# dexterity.net
KiCad netlist of a schematic drawn in EAGLE
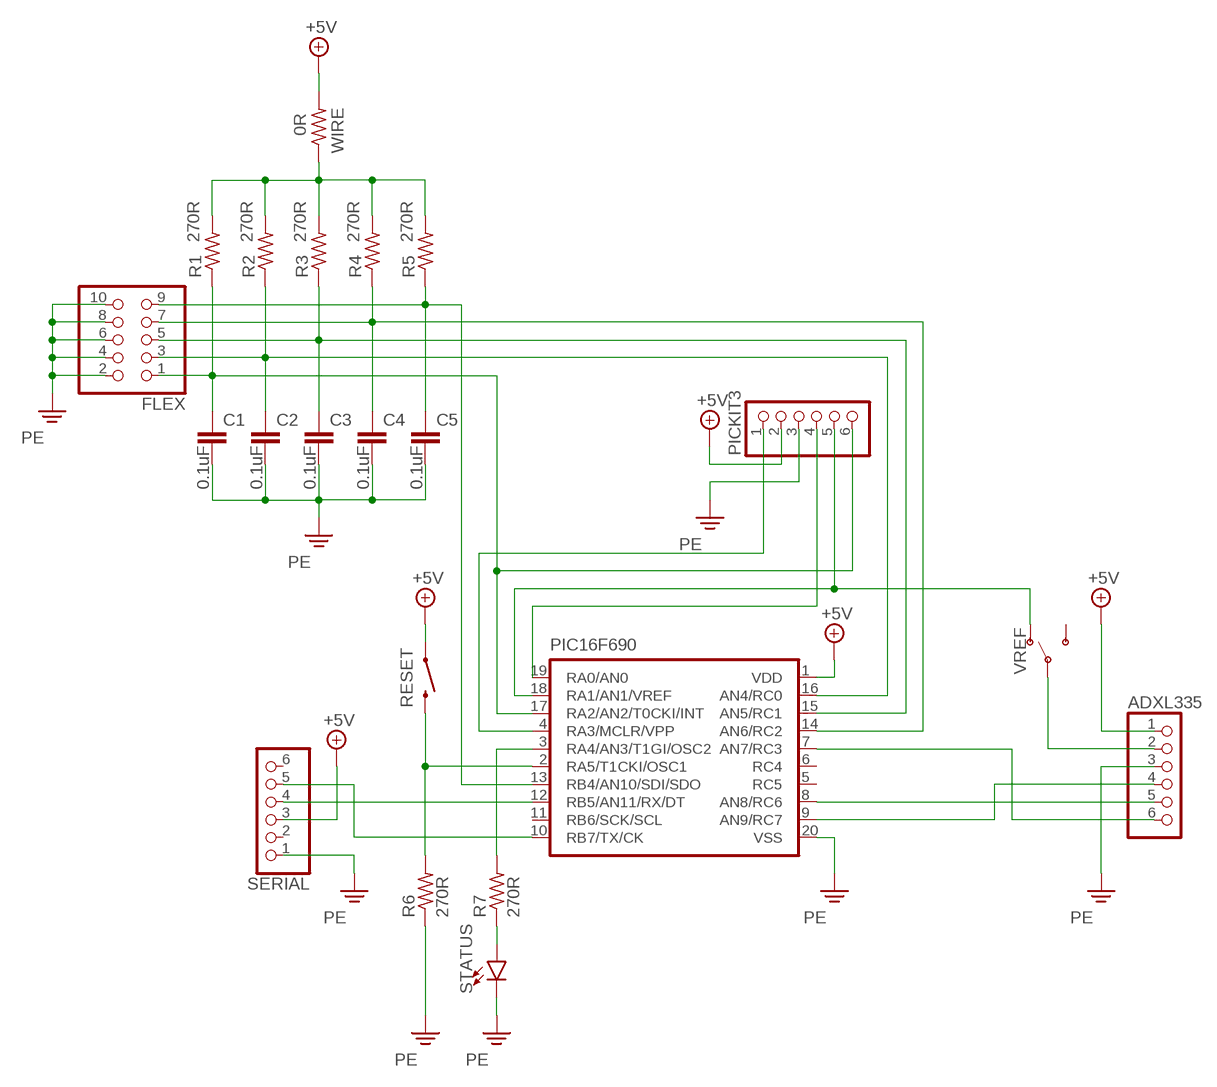
[diagram p0: schematic, sheet 1]

(export (version "E")
  (design (tool "Eeschema 10.0.6"))
  (components
    (comp (ref "ADXL335")
      (value "PINHD-1X6/90")
      (footprint "eagle-import:1X06_90")
      (libsource (lib "eagle-import") (part "PINHD-1X6/90"))
    )
    (comp (ref "C1")
      (value "0.1uF")
      (footprint "eagle-import:C050-025X075")
      (libsource (lib "eagle-import") (part "C-EU050-025X075"))
    )
    (comp (ref "C2")
      (value "0.1uF")
      (footprint "eagle-import:C050-025X075")
      (libsource (lib "eagle-import") (part "C-EU050-025X075"))
    )
    (comp (ref "C3")
      (value "0.1uF")
      (footprint "eagle-import:C050-025X075")
      (libsource (lib "eagle-import") (part "C-EU050-025X075"))
    )
    (comp (ref "C4")
      (value "0.1uF")
      (footprint "eagle-import:C050-025X075")
      (libsource (lib "eagle-import") (part "C-EU050-025X075"))
    )
    (comp (ref "C5")
      (value "0.1uF")
      (footprint "eagle-import:C050-025X075")
      (libsource (lib "eagle-import") (part "C-EU050-025X075"))
    )
    (comp (ref "FLEX")
      (value "PINHD-2X5/90")
      (footprint "eagle-import:2X05_90")
      (libsource (lib "eagle-import") (part "PINHD-2X5/90"))
    )
    (comp (ref "PIC16F690")
      (value "PIC16F6XX")
      (footprint "eagle-import:DIL20")
      (libsource (lib "eagle-import") (part "PIC16F6XX"))
    )
    (comp (ref "PICKIT3")
      (value "PINHD-1X6")
      (footprint "eagle-import:1X06")
      (libsource (lib "eagle-import") (part "PINHD-1X6"))
    )
    (comp (ref "R1")
      (value "270R")
      (footprint "eagle-import:0207_7")
      (libsource (lib "eagle-import") (part "R-US_0207/7"))
    )
    (comp (ref "R2")
      (value "270R")
      (footprint "eagle-import:0207_7")
      (libsource (lib "eagle-import") (part "R-US_0207/7"))
    )
    (comp (ref "R3")
      (value "270R")
      (footprint "eagle-import:0207_7")
      (libsource (lib "eagle-import") (part "R-US_0207/7"))
    )
    (comp (ref "R4")
      (value "270R")
      (footprint "eagle-import:0207_7")
      (libsource (lib "eagle-import") (part "R-US_0207/7"))
    )
    (comp (ref "R5")
      (value "270R")
      (footprint "eagle-import:0207_7")
      (libsource (lib "eagle-import") (part "R-US_0207/7"))
    )
    (comp (ref "R6")
      (value "270R")
      (footprint "eagle-import:0207_7")
      (libsource (lib "eagle-import") (part "R-US_0207/7"))
    )
    (comp (ref "R7")
      (value "270R")
      (footprint "eagle-import:0207_7")
      (libsource (lib "eagle-import") (part "R-US_0207/7"))
    )
    (comp (ref "RESET")
      (value "MOMENTARY-SWITCH-SPST-PTH-6.0MM")
      (footprint "eagle-import:TACTILE_SWITCH_PTH_6.0MM")
      (libsource (lib "eagle-import") (part "MOMENTARY-SWITCH-SPST-PTH-6.0MM"))
    )
    (comp (ref "SERIAL")
      (value "PINHD-1X6/90")
      (footprint "eagle-import:1X06_90")
      (libsource (lib "eagle-import") (part "PINHD-1X6/90"))
    )
    (comp (ref "STATUS")
      (value "LED3MM")
      (footprint "eagle-import:LED_3MM")
      (libsource (lib "eagle-import") (part "LED3MM"))
    )
    (comp (ref "VREF")
      (value "SWITCH-SPDT-PTH-11.6X4.0MM")
      (footprint "eagle-import:SWITCH_SPDT_PTH_11.6X4.0MM")
      (libsource (lib "eagle-import") (part "SWITCH-SPDT-PTH-11.6X4.0MM"))
    )
    (comp (ref "WIRE")
      (value "0R")
      (footprint "eagle-import:0207_7")
      (libsource (lib "eagle-import") (part "R-US_0207/7"))
    )
  )
  (nets
    (net (code "1") (name "+5V") (class "Default")
      (node (ref "ADXL335") (pin "1") (pinfunction "1_1") (pintype "passive"))
      (node (ref "PIC16F690") (pin "1") (pinfunction "VDD_1") (pintype "power_in"))
      (node (ref "PICKIT3") (pin "2") (pinfunction "2_2") (pintype "passive"))
      (node (ref "R1") (pin "2") (pinfunction "2_2") (pintype "passive"))
      (node (ref "R2") (pin "2") (pinfunction "2_2") (pintype "passive"))
      (node (ref "R3") (pin "2") (pinfunction "2_2") (pintype "passive"))
      (node (ref "R4") (pin "2") (pinfunction "2_2") (pintype "passive"))
      (node (ref "R5") (pin "2") (pinfunction "2_2") (pintype "passive"))
      (node (ref "RESET") (pin "1") (pinfunction "1_1") (pintype "passive"))
      (node (ref "SERIAL") (pin "3") (pinfunction "3_3") (pintype "passive"))
      (node (ref "WIRE") (pin "1") (pinfunction "1_1") (pintype "passive"))
      (node (ref "WIRE") (pin "2") (pinfunction "2_2") (pintype "passive"))
    )
    (net (code "2") (name "Net-(PIC16F690-AN4{slash}RC0)") (class "Default")
      (node (ref "C2") (pin "1") (pinfunction "1_1") (pintype "passive"))
      (node (ref "FLEX") (pin "3") (pinfunction "3_3") (pintype "passive"))
      (node (ref "PIC16F690") (pin "16") (pinfunction "AN4/RC0_16") (pintype "bidirectional"))
      (node (ref "R2") (pin "1") (pinfunction "1_1") (pintype "passive"))
    )
    (net (code "3") (name "Net-(PIC16F690-AN5{slash}RC1)") (class "Default")
      (node (ref "C3") (pin "1") (pinfunction "1_1") (pintype "passive"))
      (node (ref "FLEX") (pin "5") (pinfunction "5_5") (pintype "passive"))
      (node (ref "PIC16F690") (pin "15") (pinfunction "AN5/RC1_15") (pintype "bidirectional"))
      (node (ref "R3") (pin "1") (pinfunction "1_1") (pintype "passive"))
    )
    (net (code "4") (name "Net-(PIC16F690-AN6{slash}RC2)") (class "Default")
      (node (ref "C4") (pin "1") (pinfunction "1_1") (pintype "passive"))
      (node (ref "FLEX") (pin "7") (pinfunction "7_7") (pintype "passive"))
      (node (ref "PIC16F690") (pin "14") (pinfunction "AN6/RC2_14") (pintype "bidirectional"))
      (node (ref "R4") (pin "1") (pinfunction "1_1") (pintype "passive"))
    )
    (net (code "5") (name "Net-(PIC16F690-AN7{slash}RC3)") (class "Default")
      (node (ref "ADXL335") (pin "6") (pinfunction "6_6") (pintype "passive"))
      (node (ref "PIC16F690") (pin "7") (pinfunction "AN7/RC3_7") (pintype "bidirectional"))
    )
    (net (code "6") (name "Net-(PIC16F690-AN8{slash}RC6)") (class "Default")
      (node (ref "ADXL335") (pin "5") (pinfunction "5_5") (pintype "passive"))
      (node (ref "PIC16F690") (pin "8") (pinfunction "AN8/RC6_8") (pintype "bidirectional"))
    )
    (net (code "7") (name "Net-(PIC16F690-AN9{slash}RC7)") (class "Default")
      (node (ref "ADXL335") (pin "4") (pinfunction "4_4") (pintype "passive"))
      (node (ref "PIC16F690") (pin "9") (pinfunction "AN9/RC7_9") (pintype "bidirectional"))
    )
    (net (code "8") (name "Net-(PIC16F690-RA0{slash}AN0)") (class "Default")
      (node (ref "PIC16F690") (pin "19") (pinfunction "RA0/AN0_19") (pintype "bidirectional"))
      (node (ref "PICKIT3") (pin "4") (pinfunction "4_4") (pintype "passive"))
    )
    (net (code "9") (name "Net-(PIC16F690-RA1{slash}AN1{slash}VREF)") (class "Default")
      (node (ref "PIC16F690") (pin "18") (pinfunction "RA1/AN1/VREF_18") (pintype "bidirectional"))
      (node (ref "PICKIT3") (pin "5") (pinfunction "5_5") (pintype "passive"))
      (node (ref "VREF") (pin "1") (pinfunction "O_1") (pintype "passive"))
    )
    (net (code "10") (name "Net-(PIC16F690-RA2{slash}AN2{slash}T0CKI{slash}INT)") (class "Default")
      (node (ref "C1") (pin "1") (pinfunction "1_1") (pintype "passive"))
      (node (ref "FLEX") (pin "1") (pinfunction "1_1") (pintype "passive"))
      (node (ref "PIC16F690") (pin "17") (pinfunction "RA2/AN2/T0CKI/INT_17") (pintype "bidirectional"))
      (node (ref "PICKIT3") (pin "6") (pinfunction "6_6") (pintype "passive"))
      (node (ref "R1") (pin "1") (pinfunction "1_1") (pintype "passive"))
    )
    (net (code "11") (name "Net-(PIC16F690-RA3{slash}MCLR{slash}VPP)") (class "Default")
      (node (ref "PIC16F690") (pin "4") (pinfunction "RA3/MCLR/VPP_4") (pintype "input"))
      (node (ref "PICKIT3") (pin "1") (pinfunction "1_1") (pintype "passive"))
    )
    (net (code "12") (name "Net-(PIC16F690-RA4{slash}AN3{slash}T1GI{slash}OSC2)") (class "Default")
      (node (ref "PIC16F690") (pin "3") (pinfunction "RA4/AN3/T1GI/OSC2_3") (pintype "bidirectional"))
      (node (ref "R7") (pin "2") (pinfunction "2_2") (pintype "passive"))
    )
    (net (code "13") (name "Net-(PIC16F690-RA5{slash}T1CKI{slash}OSC1)") (class "Default")
      (node (ref "PIC16F690") (pin "2") (pinfunction "RA5/T1CKI/OSC1_2") (pintype "bidirectional"))
      (node (ref "R6") (pin "2") (pinfunction "2_2") (pintype "passive"))
      (node (ref "RESET") (pin "3") (pinfunction "2_3") (pintype "passive"))
    )
    (net (code "14") (name "Net-(PIC16F690-RB4{slash}AN10{slash}SDI{slash}SDO)") (class "Default")
      (node (ref "C5") (pin "1") (pinfunction "1_1") (pintype "passive"))
      (node (ref "FLEX") (pin "9") (pinfunction "9_9") (pintype "passive"))
      (node (ref "PIC16F690") (pin "13") (pinfunction "RB4/AN10/SDI/SDO_13") (pintype "bidirectional"))
      (node (ref "R5") (pin "1") (pinfunction "1_1") (pintype "passive"))
    )
    (net (code "15") (name "Net-(PIC16F690-RB5{slash}AN11{slash}RX{slash}DT)") (class "Default")
      (node (ref "PIC16F690") (pin "12") (pinfunction "RB5/AN11/RX/DT_12") (pintype "bidirectional"))
      (node (ref "SERIAL") (pin "4") (pinfunction "4_4") (pintype "passive"))
    )
    (net (code "16") (name "Net-(PIC16F690-RB7{slash}TX{slash}CK)") (class "Default")
      (node (ref "PIC16F690") (pin "10") (pinfunction "RB7/TX/CK_10") (pintype "bidirectional"))
      (node (ref "SERIAL") (pin "5") (pinfunction "5_5") (pintype "passive"))
    )
    (net (code "17") (name "Net-(R7-Pad1)") (class "Default")
      (node (ref "R7") (pin "1") (pinfunction "1_1") (pintype "passive"))
      (node (ref "STATUS") (pin "A") (pinfunction "A_A") (pintype "passive"))
    )
    (net (code "18") (name "Net-(VREF-P)") (class "Default")
      (node (ref "ADXL335") (pin "2") (pinfunction "2_2") (pintype "passive"))
      (node (ref "VREF") (pin "2") (pinfunction "P_2") (pintype "passive"))
    )
    (net (code "19") (name "PE") (class "Default")
      (node (ref "ADXL335") (pin "3") (pinfunction "3_3") (pintype "passive"))
      (node (ref "C1") (pin "2") (pinfunction "2_2") (pintype "passive"))
      (node (ref "C2") (pin "2") (pinfunction "2_2") (pintype "passive"))
      (node (ref "C3") (pin "2") (pinfunction "2_2") (pintype "passive"))
      (node (ref "C4") (pin "2") (pinfunction "2_2") (pintype "passive"))
      (node (ref "C5") (pin "2") (pinfunction "2_2") (pintype "passive"))
      (node (ref "FLEX") (pin "10") (pinfunction "10_10") (pintype "passive"))
      (node (ref "FLEX") (pin "2") (pinfunction "2_2") (pintype "passive"))
      (node (ref "FLEX") (pin "4") (pinfunction "4_4") (pintype "passive"))
      (node (ref "FLEX") (pin "6") (pinfunction "6_6") (pintype "passive"))
      (node (ref "FLEX") (pin "8") (pinfunction "8_8") (pintype "passive"))
      (node (ref "PIC16F690") (pin "20") (pinfunction "VSS_20") (pintype "power_in"))
      (node (ref "PICKIT3") (pin "3") (pinfunction "3_3") (pintype "passive"))
      (node (ref "R6") (pin "1") (pinfunction "1_1") (pintype "passive"))
      (node (ref "SERIAL") (pin "1") (pinfunction "1_1") (pintype "passive"))
      (node (ref "STATUS") (pin "K") (pinfunction "C_K") (pintype "passive"))
    )
    (net (code "20") (name "unconnected-(PIC16F690-RB6{slash}SCK{slash}SCL-Pad11)") (class "Default")
      (node (ref "PIC16F690") (pin "11") (pinfunction "RB6/SCK/SCL_11") (pintype "bidirectional"))
    )
    (net (code "21") (name "unconnected-(PIC16F690-RC4-Pad6)") (class "Default")
      (node (ref "PIC16F690") (pin "6") (pinfunction "RC4_6") (pintype "bidirectional"))
    )
    (net (code "22") (name "unconnected-(PIC16F690-RC5-Pad5)") (class "Default")
      (node (ref "PIC16F690") (pin "5") (pinfunction "RC5_5") (pintype "bidirectional"))
    )
    (net (code "23") (name "unconnected-(SERIAL-Pad2)") (class "Default")
      (node (ref "SERIAL") (pin "2") (pinfunction "2_2") (pintype "passive"))
    )
    (net (code "24") (name "unconnected-(SERIAL-Pad6)") (class "Default")
      (node (ref "SERIAL") (pin "6") (pinfunction "6_6") (pintype "passive"))
    )
    (net (code "25") (name "unconnected-(VREF-S-Pad3)") (class "Default")
      (node (ref "VREF") (pin "3") (pinfunction "S_3") (pintype "passive"))
    )
  )
)
